# Bodenplatine.net
KiCad netlist of a schematic drawn in EAGLE
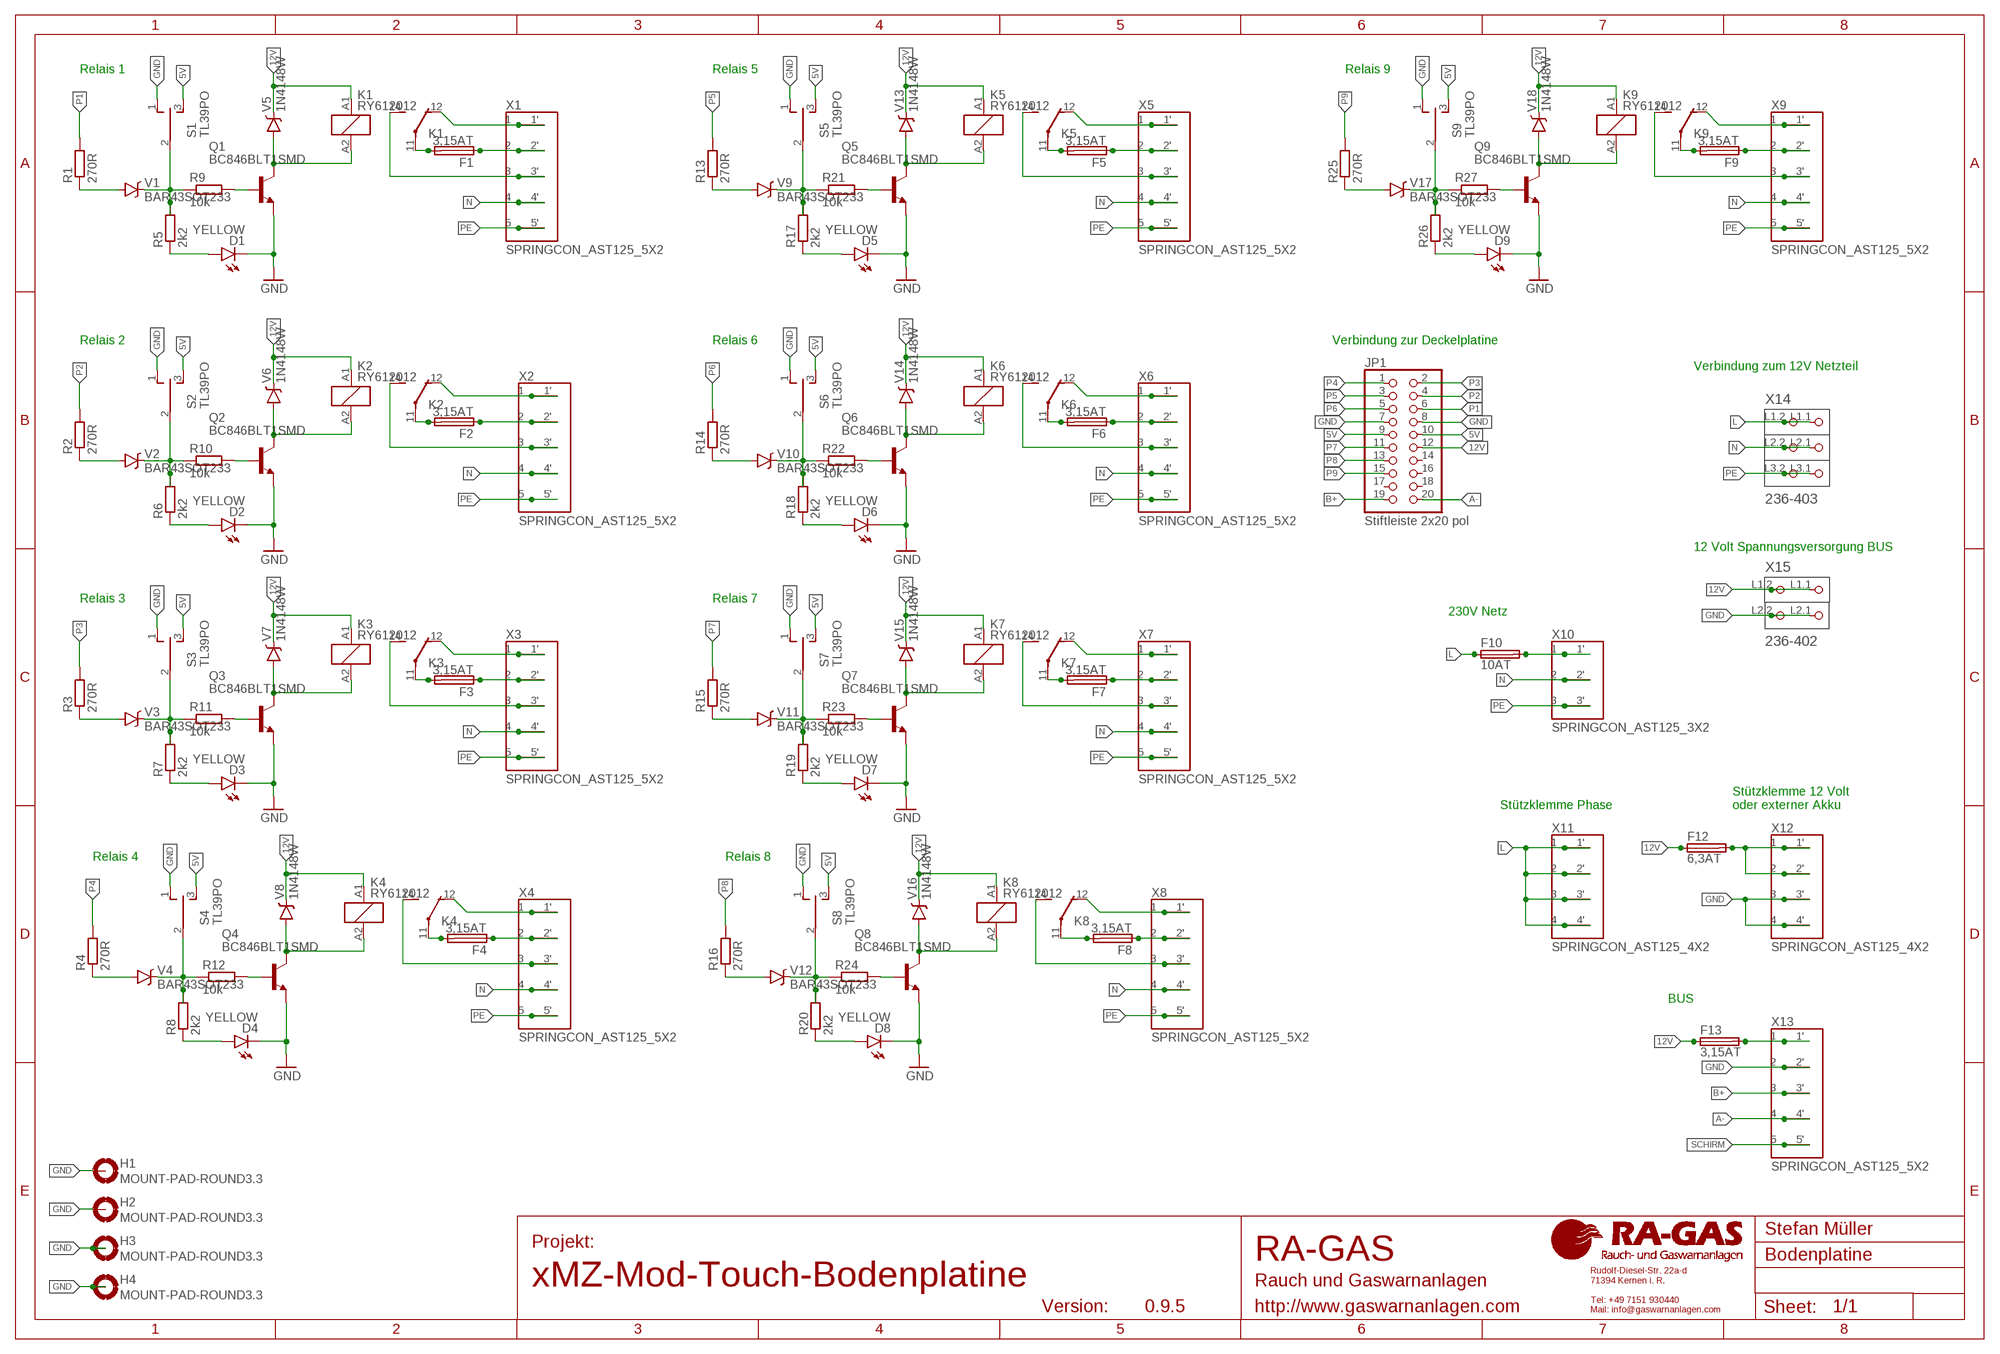
[diagram p0: schematic, sheet 1]

(export (version "E")
  (design (tool "Eeschema 10.0.6"))
  (components
    (comp (ref "D1")
      (value "YELLOW")
      (footprint "eagle-import:LED-1206")
      (fields (field (name "MF") "KINGBRIGHT") (field (name "MPN") "KP-3216SYC"))
      (libsource (lib "eagle-import") (part "LED-YELLOWLARGE"))
    )
    (comp (ref "D2")
      (value "YELLOW")
      (footprint "eagle-import:LED-1206")
      (fields (field (name "MF") "KINGBRIGHT") (field (name "MPN") "KP-3216SYC"))
      (libsource (lib "eagle-import") (part "LED-YELLOWLARGE"))
    )
    (comp (ref "D3")
      (value "YELLOW")
      (footprint "eagle-import:LED-1206")
      (fields (field (name "MF") "KINGBRIGHT") (field (name "MPN") "KP-3216SYC"))
      (libsource (lib "eagle-import") (part "LED-YELLOWLARGE"))
    )
    (comp (ref "D4")
      (value "YELLOW")
      (footprint "eagle-import:LED-1206")
      (fields (field (name "MF") "KINGBRIGHT") (field (name "MPN") "KP-3216SYC"))
      (libsource (lib "eagle-import") (part "LED-YELLOWLARGE"))
    )
    (comp (ref "D5")
      (value "YELLOW")
      (footprint "eagle-import:LED-1206")
      (fields (field (name "MF") "KINGBRIGHT") (field (name "MPN") "KP-3216SYC"))
      (libsource (lib "eagle-import") (part "LED-YELLOWLARGE"))
    )
    (comp (ref "D6")
      (value "YELLOW")
      (footprint "eagle-import:LED-1206")
      (fields (field (name "MF") "KINGBRIGHT") (field (name "MPN") "KP-3216SYC"))
      (libsource (lib "eagle-import") (part "LED-YELLOWLARGE"))
    )
    (comp (ref "D7")
      (value "YELLOW")
      (footprint "eagle-import:LED-1206")
      (fields (field (name "MF") "KINGBRIGHT") (field (name "MPN") "KP-3216SYC"))
      (libsource (lib "eagle-import") (part "LED-YELLOWLARGE"))
    )
    (comp (ref "D8")
      (value "YELLOW")
      (footprint "eagle-import:LED-1206")
      (fields (field (name "MF") "KINGBRIGHT") (field (name "MPN") "KP-3216SYC"))
      (libsource (lib "eagle-import") (part "LED-YELLOWLARGE"))
    )
    (comp (ref "D9")
      (value "YELLOW")
      (footprint "eagle-import:LED-1206")
      (fields (field (name "MF") "KINGBRIGHT") (field (name "MPN") "KP-3216SYC"))
      (libsource (lib "eagle-import") (part "LED-YELLOWLARGE"))
    )
    (comp (ref "F1")
      (value "3,15AT")
      (footprint "eagle-import:FPG4")
      (libsource (lib "eagle-import") (part "FPG4"))
    )
    (comp (ref "F2")
      (value "3,15AT")
      (footprint "eagle-import:FPG4")
      (libsource (lib "eagle-import") (part "FPG4"))
    )
    (comp (ref "F3")
      (value "3,15AT")
      (footprint "eagle-import:FPG4")
      (libsource (lib "eagle-import") (part "FPG4"))
    )
    (comp (ref "F4")
      (value "3,15AT")
      (footprint "eagle-import:FPG4")
      (libsource (lib "eagle-import") (part "FPG4"))
    )
    (comp (ref "F5")
      (value "3,15AT")
      (footprint "eagle-import:FPG4")
      (libsource (lib "eagle-import") (part "FPG4"))
    )
    (comp (ref "F6")
      (value "3,15AT")
      (footprint "eagle-import:FPG4")
      (libsource (lib "eagle-import") (part "FPG4"))
    )
    (comp (ref "F7")
      (value "3,15AT")
      (footprint "eagle-import:FPG4")
      (libsource (lib "eagle-import") (part "FPG4"))
    )
    (comp (ref "F8")
      (value "3,15AT")
      (footprint "eagle-import:FPG4")
      (libsource (lib "eagle-import") (part "FPG4"))
    )
    (comp (ref "F9")
      (value "3,15AT")
      (footprint "eagle-import:FPG4")
      (libsource (lib "eagle-import") (part "FPG4"))
    )
    (comp (ref "F10")
      (value "10AT")
      (footprint "eagle-import:FPG4")
      (libsource (lib "eagle-import") (part "FPG4"))
    )
    (comp (ref "F12")
      (value "6,3AT")
      (footprint "eagle-import:FPG4")
      (libsource (lib "eagle-import") (part "FPG4"))
    )
    (comp (ref "F13")
      (value "3,15AT")
      (footprint "eagle-import:FPG4")
      (libsource (lib "eagle-import") (part "FPG4"))
    )
    (comp (ref "H1")
      (value "MOUNT-PAD-ROUND3.3")
      (footprint "eagle-import:3,3-PAD")
      (libsource (lib "eagle-import") (part "MOUNT-PAD-ROUND3.3"))
    )
    (comp (ref "H2")
      (value "MOUNT-PAD-ROUND3.3")
      (footprint "eagle-import:3,3-PAD")
      (libsource (lib "eagle-import") (part "MOUNT-PAD-ROUND3.3"))
    )
    (comp (ref "H3")
      (value "MOUNT-PAD-ROUND3.3")
      (footprint "eagle-import:3,3-PAD")
      (libsource (lib "eagle-import") (part "MOUNT-PAD-ROUND3.3"))
    )
    (comp (ref "H4")
      (value "MOUNT-PAD-ROUND3.3")
      (footprint "eagle-import:3,3-PAD")
      (libsource (lib "eagle-import") (part "MOUNT-PAD-ROUND3.3"))
    )
    (comp (ref "JP1")
      (value "Stiftleiste 2x20 pol")
      (footprint "eagle-import:2X10")
      (fields (field (name "MF") "TE CONNECTIVITY / AMP") (field (name "MPN") "825440-5"))
      (libsource (lib "eagle-import") (part "PINHD-2X10"))
    )
    (comp (ref "K1")
      (value "RY612012")
      (footprint "eagle-import:RY-II")
      (fields
        (field (name "MF") "TYCO ELECTRONICS")
        (field (name "MF_1") "TE CONNECTIVITY / SCHRACK")
        (field (name "MPN") "V23061B1005A301")
        (field (name "OC_FARNELL") "1023958")
      )
      (libsource (lib "eagle-import") (part "RY?162012"))
    )
    (comp (ref "K2")
      (value "RY612012")
      (footprint "eagle-import:RY-II")
      (fields
        (field (name "MF") "TYCO ELECTRONICS")
        (field (name "MF_1") "TE CONNECTIVITY / SCHRACK")
        (field (name "MPN") "V23061B1005A301")
        (field (name "OC_FARNELL") "1023958")
      )
      (libsource (lib "eagle-import") (part "RY?162012"))
    )
    (comp (ref "K3")
      (value "RY612012")
      (footprint "eagle-import:RY-II")
      (fields
        (field (name "MF") "TYCO ELECTRONICS")
        (field (name "MF_1") "TE CONNECTIVITY / SCHRACK")
        (field (name "MPN") "V23061B1005A301")
        (field (name "OC_FARNELL") "1023958")
      )
      (libsource (lib "eagle-import") (part "RY?162012"))
    )
    (comp (ref "K4")
      (value "RY612012")
      (footprint "eagle-import:RY-II")
      (fields
        (field (name "MF") "TYCO ELECTRONICS")
        (field (name "MF_1") "TE CONNECTIVITY / SCHRACK")
        (field (name "MPN") "V23061B1005A301")
        (field (name "OC_FARNELL") "1023958")
      )
      (libsource (lib "eagle-import") (part "RY?162012"))
    )
    (comp (ref "K5")
      (value "RY612012")
      (footprint "eagle-import:RY-II")
      (fields
        (field (name "MF") "TYCO ELECTRONICS")
        (field (name "MF_1") "TE CONNECTIVITY / SCHRACK")
        (field (name "MPN") "V23061B1005A301")
        (field (name "OC_FARNELL") "1023958")
      )
      (libsource (lib "eagle-import") (part "RY?162012"))
    )
    (comp (ref "K6")
      (value "RY612012")
      (footprint "eagle-import:RY-II")
      (fields
        (field (name "MF") "TYCO ELECTRONICS")
        (field (name "MF_1") "TE CONNECTIVITY / SCHRACK")
        (field (name "MPN") "V23061B1005A301")
        (field (name "OC_FARNELL") "1023958")
      )
      (libsource (lib "eagle-import") (part "RY?162012"))
    )
    (comp (ref "K7")
      (value "RY612012")
      (footprint "eagle-import:RY-II")
      (fields
        (field (name "MF") "TYCO ELECTRONICS")
        (field (name "MF_1") "TE CONNECTIVITY / SCHRACK")
        (field (name "MPN") "V23061B1005A301")
        (field (name "OC_FARNELL") "1023958")
      )
      (libsource (lib "eagle-import") (part "RY?162012"))
    )
    (comp (ref "K8")
      (value "RY612012")
      (footprint "eagle-import:RY-II")
      (fields
        (field (name "MF") "TYCO ELECTRONICS")
        (field (name "MF_1") "TE CONNECTIVITY / SCHRACK")
        (field (name "MPN") "V23061B1005A301")
        (field (name "OC_FARNELL") "1023958")
      )
      (libsource (lib "eagle-import") (part "RY?162012"))
    )
    (comp (ref "K9")
      (value "RY612012")
      (footprint "eagle-import:RY-II")
      (fields
        (field (name "MF") "TYCO ELECTRONICS")
        (field (name "MF_1") "TE CONNECTIVITY / SCHRACK")
        (field (name "MPN") "V23061B1005A301")
        (field (name "OC_FARNELL") "1023958")
      )
      (libsource (lib "eagle-import") (part "RY?162012"))
    )
    (comp (ref "Q1")
      (value "BC846BLT1SMD")
      (footprint "eagle-import:SOT23")
      (fields (field (name "MF") "ON SEMICONDUCTOR") (field (name "MPN") "BC846BWT1G"))
      (libsource (lib "eagle-import") (part "BC846SMDBLT1"))
    )
    (comp (ref "Q2")
      (value "BC846BLT1SMD")
      (footprint "eagle-import:SOT23")
      (fields (field (name "MF") "ON SEMICONDUCTOR") (field (name "MPN") "BC846BWT1G"))
      (libsource (lib "eagle-import") (part "BC846SMDBLT1"))
    )
    (comp (ref "Q3")
      (value "BC846BLT1SMD")
      (footprint "eagle-import:SOT23")
      (fields (field (name "MF") "ON SEMICONDUCTOR") (field (name "MPN") "BC846BWT1G"))
      (libsource (lib "eagle-import") (part "BC846SMDBLT1"))
    )
    (comp (ref "Q4")
      (value "BC846BLT1SMD")
      (footprint "eagle-import:SOT23")
      (fields (field (name "MF") "ON SEMICONDUCTOR") (field (name "MPN") "BC846BWT1G"))
      (libsource (lib "eagle-import") (part "BC846SMDBLT1"))
    )
    (comp (ref "Q5")
      (value "BC846BLT1SMD")
      (footprint "eagle-import:SOT23")
      (fields (field (name "MF") "ON SEMICONDUCTOR") (field (name "MPN") "BC846BWT1G"))
      (libsource (lib "eagle-import") (part "BC846SMDBLT1"))
    )
    (comp (ref "Q6")
      (value "BC846BLT1SMD")
      (footprint "eagle-import:SOT23")
      (fields (field (name "MF") "ON SEMICONDUCTOR") (field (name "MPN") "BC846BWT1G"))
      (libsource (lib "eagle-import") (part "BC846SMDBLT1"))
    )
    (comp (ref "Q7")
      (value "BC846BLT1SMD")
      (footprint "eagle-import:SOT23")
      (fields (field (name "MF") "ON SEMICONDUCTOR") (field (name "MPN") "BC846BWT1G"))
      (libsource (lib "eagle-import") (part "BC846SMDBLT1"))
    )
    (comp (ref "Q8")
      (value "BC846BLT1SMD")
      (footprint "eagle-import:SOT23")
      (fields (field (name "MF") "ON SEMICONDUCTOR") (field (name "MPN") "BC846BWT1G"))
      (libsource (lib "eagle-import") (part "BC846SMDBLT1"))
    )
    (comp (ref "Q9")
      (value "BC846BLT1SMD")
      (footprint "eagle-import:SOT23")
      (fields (field (name "MF") "ON SEMICONDUCTOR") (field (name "MPN") "BC846BWT1G"))
      (libsource (lib "eagle-import") (part "BC846SMDBLT1"))
    )
    (comp (ref "R1")
      (value "270R")
      (footprint "eagle-import:M0805")
      (fields (field (name "MF") "MULTICOMP") (field (name "MPN") "MC01W08055270R"))
      (libsource (lib "eagle-import") (part "R-EU_M0805"))
    )
    (comp (ref "R2")
      (value "270R")
      (footprint "eagle-import:M0805")
      (fields (field (name "MF") "MULTICOMP") (field (name "MPN") "MC01W08055270R"))
      (libsource (lib "eagle-import") (part "R-EU_M0805"))
    )
    (comp (ref "R3")
      (value "270R")
      (footprint "eagle-import:M0805")
      (fields (field (name "MF") "MULTICOMP") (field (name "MPN") "MC01W08055270R"))
      (libsource (lib "eagle-import") (part "R-EU_M0805"))
    )
    (comp (ref "R4")
      (value "270R")
      (footprint "eagle-import:M0805")
      (fields (field (name "MF") "MULTICOMP") (field (name "MPN") "MC01W08055270R"))
      (libsource (lib "eagle-import") (part "R-EU_M0805"))
    )
    (comp (ref "R5")
      (value "2k2")
      (footprint "eagle-import:R0603")
      (fields (field (name "MF") "MULTICOMP") (field (name "MPN") "MC0063W060352K2"))
      (libsource (lib "eagle-import") (part "R-EU_R0603"))
    )
    (comp (ref "R6")
      (value "2k2")
      (footprint "eagle-import:R0603")
      (fields (field (name "MF") "MULTICOMP") (field (name "MPN") "MC0063W060352K2"))
      (libsource (lib "eagle-import") (part "R-EU_R0603"))
    )
    (comp (ref "R7")
      (value "2k2")
      (footprint "eagle-import:R0603")
      (fields (field (name "MF") "MULTICOMP") (field (name "MPN") "MC0063W060352K2"))
      (libsource (lib "eagle-import") (part "R-EU_R0603"))
    )
    (comp (ref "R8")
      (value "2k2")
      (footprint "eagle-import:R0603")
      (fields (field (name "MF") "MULTICOMP") (field (name "MPN") "MC0063W060352K2"))
      (libsource (lib "eagle-import") (part "R-EU_R0603"))
    )
    (comp (ref "R9")
      (value "10k")
      (footprint "eagle-import:R0603")
      (fields (field (name "MF") "TE CONNECTIVITY / NEOHM") (field (name "MPN") "CPF0603B10KE1"))
      (libsource (lib "eagle-import") (part "R-EU_R0603"))
    )
    (comp (ref "R10")
      (value "10k")
      (footprint "eagle-import:R0603")
      (fields (field (name "MF") "TE CONNECTIVITY / NEOHM") (field (name "MPN") "CPF0603B10KE1"))
      (libsource (lib "eagle-import") (part "R-EU_R0603"))
    )
    (comp (ref "R11")
      (value "10k")
      (footprint "eagle-import:R0603")
      (fields (field (name "MF") "TE CONNECTIVITY / NEOHM") (field (name "MPN") "CPF0603B10KE1"))
      (libsource (lib "eagle-import") (part "R-EU_R0603"))
    )
    (comp (ref "R12")
      (value "10k")
      (footprint "eagle-import:R0603")
      (fields (field (name "MF") "TE CONNECTIVITY / NEOHM") (field (name "MPN") "CPF0603B10KE1"))
      (libsource (lib "eagle-import") (part "R-EU_R0603"))
    )
    (comp (ref "R13")
      (value "270R")
      (footprint "eagle-import:M0805")
      (fields (field (name "MF") "MULTICOMP") (field (name "MPN") "MC01W08055270R"))
      (libsource (lib "eagle-import") (part "R-EU_M0805"))
    )
    (comp (ref "R14")
      (value "270R")
      (footprint "eagle-import:M0805")
      (fields (field (name "MF") "MULTICOMP") (field (name "MPN") "MC01W08055270R"))
      (libsource (lib "eagle-import") (part "R-EU_M0805"))
    )
    (comp (ref "R15")
      (value "270R")
      (footprint "eagle-import:M0805")
      (fields (field (name "MF") "MULTICOMP") (field (name "MPN") "MC01W08055270R"))
      (libsource (lib "eagle-import") (part "R-EU_M0805"))
    )
    (comp (ref "R16")
      (value "270R")
      (footprint "eagle-import:M0805")
      (fields (field (name "MF") "MULTICOMP") (field (name "MPN") "MC01W08055270R"))
      (libsource (lib "eagle-import") (part "R-EU_M0805"))
    )
    (comp (ref "R17")
      (value "2k2")
      (footprint "eagle-import:R0603")
      (fields (field (name "MF") "MULTICOMP") (field (name "MPN") "MC0063W060352K2"))
      (libsource (lib "eagle-import") (part "R-EU_R0603"))
    )
    (comp (ref "R18")
      (value "2k2")
      (footprint "eagle-import:R0603")
      (fields (field (name "MF") "MULTICOMP") (field (name "MPN") "MC0063W060352K2"))
      (libsource (lib "eagle-import") (part "R-EU_R0603"))
    )
    (comp (ref "R19")
      (value "2k2")
      (footprint "eagle-import:R0603")
      (fields (field (name "MF") "MULTICOMP") (field (name "MPN") "MC0063W060352K2"))
      (libsource (lib "eagle-import") (part "R-EU_R0603"))
    )
    (comp (ref "R20")
      (value "2k2")
      (footprint "eagle-import:R0603")
      (fields (field (name "MF") "MULTICOMP") (field (name "MPN") "MC0063W060352K2"))
      (libsource (lib "eagle-import") (part "R-EU_R0603"))
    )
    (comp (ref "R21")
      (value "10k")
      (footprint "eagle-import:R0603")
      (fields (field (name "MF") "TE CONNECTIVITY / NEOHM") (field (name "MPN") "CPF0603B10KE1"))
      (libsource (lib "eagle-import") (part "R-EU_R0603"))
    )
    (comp (ref "R22")
      (value "10k")
      (footprint "eagle-import:R0603")
      (fields (field (name "MF") "TE CONNECTIVITY / NEOHM") (field (name "MPN") "CPF0603B10KE1"))
      (libsource (lib "eagle-import") (part "R-EU_R0603"))
    )
    (comp (ref "R23")
      (value "10k")
      (footprint "eagle-import:R0603")
      (fields (field (name "MF") "TE CONNECTIVITY / NEOHM") (field (name "MPN") "CPF0603B10KE1"))
      (libsource (lib "eagle-import") (part "R-EU_R0603"))
    )
    (comp (ref "R24")
      (value "10k")
      (footprint "eagle-import:R0603")
      (fields (field (name "MF") "TE CONNECTIVITY / NEOHM") (field (name "MPN") "CPF0603B10KE1"))
      (libsource (lib "eagle-import") (part "R-EU_R0603"))
    )
    (comp (ref "R25")
      (value "270R")
      (footprint "eagle-import:M0805")
      (fields (field (name "MF") "MULTICOMP") (field (name "MPN") "MC01W08055270R"))
      (libsource (lib "eagle-import") (part "R-EU_M0805"))
    )
    (comp (ref "R26")
      (value "2k2")
      (footprint "eagle-import:R0603")
      (fields (field (name "MF") "MULTICOMP") (field (name "MPN") "MC0063W060352K2"))
      (libsource (lib "eagle-import") (part "R-EU_R0603"))
    )
    (comp (ref "R27")
      (value "10k")
      (footprint "eagle-import:R0603")
      (fields (field (name "MF") "TE CONNECTIVITY / NEOHM") (field (name "MPN") "CPF0603B10KE1"))
      (libsource (lib "eagle-import") (part "R-EU_R0603"))
    )
    (comp (ref "S1")
      (value "TL39PO")
      (footprint "eagle-import:TL3XPO")
      (fields (field (name "MF") "TE CONNECTIVITY / ALCOSWITCH") (field (name "MPN") "A103SYCQ04"))
      (libsource (lib "eagle-import") (part "TL39PO"))
    )
    (comp (ref "S2")
      (value "TL39PO")
      (footprint "eagle-import:TL3XPO")
      (fields (field (name "MF") "TE CONNECTIVITY / ALCOSWITCH") (field (name "MPN") "A103SYCQ04"))
      (libsource (lib "eagle-import") (part "TL39PO"))
    )
    (comp (ref "S3")
      (value "TL39PO")
      (footprint "eagle-import:TL3XPO")
      (fields (field (name "MF") "TE CONNECTIVITY / ALCOSWITCH") (field (name "MPN") "A103SYCQ04"))
      (libsource (lib "eagle-import") (part "TL39PO"))
    )
    (comp (ref "S4")
      (value "TL39PO")
      (footprint "eagle-import:TL3XPO")
      (fields (field (name "MF") "TE CONNECTIVITY / ALCOSWITCH") (field (name "MPN") "A103SYCQ04"))
      (libsource (lib "eagle-import") (part "TL39PO"))
    )
    (comp (ref "S5")
      (value "TL39PO")
      (footprint "eagle-import:TL3XPO")
      (fields (field (name "MF") "TE CONNECTIVITY / ALCOSWITCH") (field (name "MPN") "A103SYCQ04"))
      (libsource (lib "eagle-import") (part "TL39PO"))
    )
    (comp (ref "S6")
      (value "TL39PO")
      (footprint "eagle-import:TL3XPO")
      (fields (field (name "MF") "TE CONNECTIVITY / ALCOSWITCH") (field (name "MPN") "A103SYCQ04"))
      (libsource (lib "eagle-import") (part "TL39PO"))
    )
    (comp (ref "S7")
      (value "TL39PO")
      (footprint "eagle-import:TL3XPO")
      (fields (field (name "MF") "TE CONNECTIVITY / ALCOSWITCH") (field (name "MPN") "A103SYCQ04"))
      (libsource (lib "eagle-import") (part "TL39PO"))
    )
    (comp (ref "S8")
      (value "TL39PO")
      (footprint "eagle-import:TL3XPO")
      (fields (field (name "MF") "TE CONNECTIVITY / ALCOSWITCH") (field (name "MPN") "A103SYCQ04"))
      (libsource (lib "eagle-import") (part "TL39PO"))
    )
    (comp (ref "S9")
      (value "TL39PO")
      (footprint "eagle-import:TL3XPO")
      (fields (field (name "MF") "TE CONNECTIVITY / ALCOSWITCH") (field (name "MPN") "A103SYCQ04"))
      (libsource (lib "eagle-import") (part "TL39PO"))
    )
    (comp (ref "V1")
      (value "BAR43SOT233")
      (footprint "eagle-import:SOT23")
      (fields (field (name "MF") "FAIRCHILD SEMICONDUCTOR") (field (name "MPN") "BAR43"))
      (libsource (lib "eagle-import") (part "BAR43SOT233"))
    )
    (comp (ref "V2")
      (value "BAR43SOT233")
      (footprint "eagle-import:SOT23")
      (fields (field (name "MF") "FAIRCHILD SEMICONDUCTOR") (field (name "MPN") "BAR43"))
      (libsource (lib "eagle-import") (part "BAR43SOT233"))
    )
    (comp (ref "V3")
      (value "BAR43SOT233")
      (footprint "eagle-import:SOT23")
      (fields (field (name "MF") "FAIRCHILD SEMICONDUCTOR") (field (name "MPN") "BAR43"))
      (libsource (lib "eagle-import") (part "BAR43SOT233"))
    )
    (comp (ref "V4")
      (value "BAR43SOT233")
      (footprint "eagle-import:SOT23")
      (fields (field (name "MF") "FAIRCHILD SEMICONDUCTOR") (field (name "MPN") "BAR43"))
      (libsource (lib "eagle-import") (part "BAR43SOT233"))
    )
    (comp (ref "V5")
      (value "1N4148W")
      (footprint "eagle-import:MINIMELF")
      (fields (field (name "MF") "VISHAY") (field (name "MPN") "LL4148-GS08"))
      (libsource (lib "eagle-import") (part "LL4148"))
    )
    (comp (ref "V6")
      (value "1N4148W")
      (footprint "eagle-import:MINIMELF")
      (fields (field (name "MF") "VISHAY") (field (name "MPN") "LL4148-GS08"))
      (libsource (lib "eagle-import") (part "LL4148"))
    )
    (comp (ref "V7")
      (value "1N4148W")
      (footprint "eagle-import:MINIMELF")
      (fields (field (name "MF") "VISHAY") (field (name "MPN") "LL4148-GS08"))
      (libsource (lib "eagle-import") (part "LL4148"))
    )
    (comp (ref "V8")
      (value "1N4148W")
      (footprint "eagle-import:MINIMELF")
      (fields (field (name "MF") "VISHAY") (field (name "MPN") "LL4148-GS08"))
      (libsource (lib "eagle-import") (part "LL4148"))
    )
    (comp (ref "V9")
      (value "BAR43SOT233")
      (footprint "eagle-import:SOT23")
      (fields (field (name "MF") "FAIRCHILD SEMICONDUCTOR") (field (name "MPN") "BAR43"))
      (libsource (lib "eagle-import") (part "BAR43SOT233"))
    )
    (comp (ref "V10")
      (value "BAR43SOT233")
      (footprint "eagle-import:SOT23")
      (fields (field (name "MF") "FAIRCHILD SEMICONDUCTOR") (field (name "MPN") "BAR43"))
      (libsource (lib "eagle-import") (part "BAR43SOT233"))
    )
    (comp (ref "V11")
      (value "BAR43SOT233")
      (footprint "eagle-import:SOT23")
      (fields (field (name "MF") "FAIRCHILD SEMICONDUCTOR") (field (name "MPN") "BAR43"))
      (libsource (lib "eagle-import") (part "BAR43SOT233"))
    )
    (comp (ref "V12")
      (value "BAR43SOT233")
      (footprint "eagle-import:SOT23")
      (fields (field (name "MF") "FAIRCHILD SEMICONDUCTOR") (field (name "MPN") "BAR43"))
      (libsource (lib "eagle-import") (part "BAR43SOT233"))
    )
    (comp (ref "V13")
      (value "1N4148W")
      (footprint "eagle-import:MINIMELF")
      (fields (field (name "MF") "VISHAY") (field (name "MPN") "LL4148-GS08"))
      (libsource (lib "eagle-import") (part "LL4148"))
    )
    (comp (ref "V14")
      (value "1N4148W")
      (footprint "eagle-import:MINIMELF")
      (fields (field (name "MF") "VISHAY") (field (name "MPN") "LL4148-GS08"))
      (libsource (lib "eagle-import") (part "LL4148"))
    )
    (comp (ref "V15")
      (value "1N4148W")
      (footprint "eagle-import:MINIMELF")
      (fields (field (name "MF") "VISHAY") (field (name "MPN") "LL4148-GS08"))
      (libsource (lib "eagle-import") (part "LL4148"))
    )
    (comp (ref "V16")
      (value "1N4148W")
      (footprint "eagle-import:MINIMELF")
      (fields (field (name "MF") "VISHAY") (field (name "MPN") "LL4148-GS08"))
      (libsource (lib "eagle-import") (part "LL4148"))
    )
    (comp (ref "V17")
      (value "BAR43SOT233")
      (footprint "eagle-import:SOT23")
      (fields (field (name "MF") "FAIRCHILD SEMICONDUCTOR") (field (name "MPN") "BAR43"))
      (libsource (lib "eagle-import") (part "BAR43SOT233"))
    )
    (comp (ref "V18")
      (value "1N4148W")
      (footprint "eagle-import:MINIMELF")
      (fields (field (name "MF") "VISHAY") (field (name "MPN") "LL4148-GS08"))
      (libsource (lib "eagle-import") (part "LL4148"))
    )
    (comp (ref "X1")
      (value "SPRINGCON_AST125_5X2")
      (footprint "eagle-import:SPRINGCON_AST125_5X2")
      (libsource (lib "eagle-import") (part "SPRINGCON_AST125_5X2"))
    )
    (comp (ref "X2")
      (value "SPRINGCON_AST125_5X2")
      (footprint "eagle-import:SPRINGCON_AST125_5X2")
      (libsource (lib "eagle-import") (part "SPRINGCON_AST125_5X2"))
    )
    (comp (ref "X3")
      (value "SPRINGCON_AST125_5X2")
      (footprint "eagle-import:SPRINGCON_AST125_5X2")
      (libsource (lib "eagle-import") (part "SPRINGCON_AST125_5X2"))
    )
    (comp (ref "X4")
      (value "SPRINGCON_AST125_5X2")
      (footprint "eagle-import:SPRINGCON_AST125_5X2")
      (libsource (lib "eagle-import") (part "SPRINGCON_AST125_5X2"))
    )
    (comp (ref "X5")
      (value "SPRINGCON_AST125_5X2")
      (footprint "eagle-import:SPRINGCON_AST125_5X2")
      (libsource (lib "eagle-import") (part "SPRINGCON_AST125_5X2"))
    )
    (comp (ref "X6")
      (value "SPRINGCON_AST125_5X2")
      (footprint "eagle-import:SPRINGCON_AST125_5X2")
      (libsource (lib "eagle-import") (part "SPRINGCON_AST125_5X2"))
    )
    (comp (ref "X7")
      (value "SPRINGCON_AST125_5X2")
      (footprint "eagle-import:SPRINGCON_AST125_5X2")
      (libsource (lib "eagle-import") (part "SPRINGCON_AST125_5X2"))
    )
    (comp (ref "X8")
      (value "SPRINGCON_AST125_5X2")
      (footprint "eagle-import:SPRINGCON_AST125_5X2")
      (libsource (lib "eagle-import") (part "SPRINGCON_AST125_5X2"))
    )
    (comp (ref "X9")
      (value "SPRINGCON_AST125_5X2")
      (footprint "eagle-import:SPRINGCON_AST125_5X2")
      (libsource (lib "eagle-import") (part "SPRINGCON_AST125_5X2"))
    )
    (comp (ref "X10")
      (value "SPRINGCON_AST125_3X2")
      (footprint "eagle-import:SPRINGCON_AST125_3X2")
      (libsource (lib "eagle-import") (part "SPRINGCON_AST125_3X2"))
    )
    (comp (ref "X11")
      (value "SPRINGCON_AST125_4X2")
      (footprint "eagle-import:SPRINGCON_AST125_4X2")
      (libsource (lib "eagle-import") (part "SPRINGCON_AST125_4X2"))
    )
    (comp (ref "X12")
      (value "SPRINGCON_AST125_4X2")
      (footprint "eagle-import:SPRINGCON_AST125_4X2")
      (libsource (lib "eagle-import") (part "SPRINGCON_AST125_4X2"))
    )
    (comp (ref "X13")
      (value "SPRINGCON_AST125_5X2")
      (footprint "eagle-import:SPRINGCON_AST125_5X2")
      (libsource (lib "eagle-import") (part "SPRINGCON_AST125_5X2"))
    )
    (comp (ref "X14")
      (value "236-403")
      (footprint "eagle-import:P-236-403")
      (fields (field (name "MF") "WAGO"))
      (libsource (lib "eagle-import") (part "236-403"))
    )
    (comp (ref "X15")
      (value "236-402")
      (footprint "eagle-import:P-236-402")
      (fields (field (name "MF") "WAGO"))
      (libsource (lib "eagle-import") (part "236-402"))
    )
  )
  (nets
    (net (code "1") (name "5V") (class "Default")
      (node (ref "JP1") (pin "10") (pinfunction "10_10") (pintype "passive"))
      (node (ref "JP1") (pin "9") (pinfunction "9_9") (pintype "passive"))
      (node (ref "S1") (pin "3") (pinfunction "S_3") (pintype "passive"))
      (node (ref "S2") (pin "3") (pinfunction "S_3") (pintype "passive"))
      (node (ref "S3") (pin "3") (pinfunction "S_3") (pintype "passive"))
      (node (ref "S4") (pin "3") (pinfunction "S_3") (pintype "passive"))
      (node (ref "S5") (pin "3") (pinfunction "S_3") (pintype "passive"))
      (node (ref "S6") (pin "3") (pinfunction "S_3") (pintype "passive"))
      (node (ref "S7") (pin "3") (pinfunction "S_3") (pintype "passive"))
      (node (ref "S8") (pin "3") (pinfunction "S_3") (pintype "passive"))
      (node (ref "S9") (pin "3") (pinfunction "S_3") (pintype "passive"))
    )
    (net (code "2") (name "12V") (class "Default")
      (node (ref "F12") (pin "1") (pinfunction "1_1") (pintype "passive"))
      (node (ref "F12") (pin "1'") (pinfunction "1_1'") (pintype "passive"))
      (node (ref "F13") (pin "1") (pinfunction "1_1") (pintype "passive"))
      (node (ref "F13") (pin "1'") (pinfunction "1_1'") (pintype "passive"))
      (node (ref "JP1") (pin "12") (pinfunction "12_12") (pintype "passive"))
      (node (ref "K1") (pin "A1") (pinfunction "1_A1") (pintype "passive"))
      (node (ref "K2") (pin "A1") (pinfunction "1_A1") (pintype "passive"))
      (node (ref "K3") (pin "A1") (pinfunction "1_A1") (pintype "passive"))
      (node (ref "K4") (pin "A1") (pinfunction "1_A1") (pintype "passive"))
      (node (ref "K5") (pin "A1") (pinfunction "1_A1") (pintype "passive"))
      (node (ref "K6") (pin "A1") (pinfunction "1_A1") (pintype "passive"))
      (node (ref "K7") (pin "A1") (pinfunction "1_A1") (pintype "passive"))
      (node (ref "K8") (pin "A1") (pinfunction "1_A1") (pintype "passive"))
      (node (ref "K9") (pin "A1") (pinfunction "1_A1") (pintype "passive"))
      (node (ref "V13") (pin "C") (pinfunction "C_C") (pintype "passive"))
      (node (ref "V14") (pin "C") (pinfunction "C_C") (pintype "passive"))
      (node (ref "V15") (pin "C") (pinfunction "C_C") (pintype "passive"))
      (node (ref "V16") (pin "C") (pinfunction "C_C") (pintype "passive"))
      (node (ref "V18") (pin "C") (pinfunction "C_C") (pintype "passive"))
      (node (ref "V5") (pin "C") (pinfunction "C_C") (pintype "passive"))
      (node (ref "V6") (pin "C") (pinfunction "C_C") (pintype "passive"))
      (node (ref "V7") (pin "C") (pinfunction "C_C") (pintype "passive"))
      (node (ref "V8") (pin "C") (pinfunction "C_C") (pintype "passive"))
      (node (ref "X15") (pin "L1.1") (pinfunction "P1.1_L1.1") (pintype "bidirectional"))
      (node (ref "X15") (pin "L1.2") (pinfunction "P1.2_L1.2") (pintype "bidirectional"))
    )
    (net (code "3") (name "A-") (class "Default")
      (node (ref "JP1") (pin "20") (pinfunction "20_20") (pintype "passive"))
      (node (ref "X13") (pin "4") (pinfunction "4_4") (pintype "passive"))
      (node (ref "X13") (pin "4'") (pinfunction "4_4'") (pintype "passive"))
    )
    (net (code "4") (name "B+") (class "Default")
      (node (ref "JP1") (pin "19") (pinfunction "19_19") (pintype "passive"))
      (node (ref "X13") (pin "3") (pinfunction "3_3") (pintype "passive"))
      (node (ref "X13") (pin "3'") (pinfunction "3_3'") (pintype "passive"))
    )
    (net (code "5") (name "GND") (class "Default")
      (node (ref "D1") (pin "C") (pinfunction "C_C") (pintype "passive"))
      (node (ref "D2") (pin "C") (pinfunction "C_C") (pintype "passive"))
      (node (ref "D3") (pin "C") (pinfunction "C_C") (pintype "passive"))
      (node (ref "D4") (pin "C") (pinfunction "C_C") (pintype "passive"))
      (node (ref "D5") (pin "C") (pinfunction "C_C") (pintype "passive"))
      (node (ref "D6") (pin "C") (pinfunction "C_C") (pintype "passive"))
      (node (ref "D7") (pin "C") (pinfunction "C_C") (pintype "passive"))
      (node (ref "D8") (pin "C") (pinfunction "C_C") (pintype "passive"))
      (node (ref "D9") (pin "C") (pinfunction "C_C") (pintype "passive"))
      (node (ref "H1") (pin "B3,3") (pinfunction "MOUNT_B3,3") (pintype "passive"))
      (node (ref "H2") (pin "B3,3") (pinfunction "MOUNT_B3,3") (pintype "passive"))
      (node (ref "H3") (pin "B3,3") (pinfunction "MOUNT_B3,3") (pintype "passive"))
      (node (ref "H4") (pin "B3,3") (pinfunction "MOUNT_B3,3") (pintype "passive"))
      (node (ref "JP1") (pin "7") (pinfunction "7_7") (pintype "passive"))
      (node (ref "JP1") (pin "8") (pinfunction "8_8") (pintype "passive"))
      (node (ref "Q1") (pin "2") (pinfunction "E_2") (pintype "passive"))
      (node (ref "Q2") (pin "2") (pinfunction "E_2") (pintype "passive"))
      (node (ref "Q3") (pin "2") (pinfunction "E_2") (pintype "passive"))
      (node (ref "Q4") (pin "2") (pinfunction "E_2") (pintype "passive"))
      (node (ref "Q5") (pin "2") (pinfunction "E_2") (pintype "passive"))
      (node (ref "Q6") (pin "2") (pinfunction "E_2") (pintype "passive"))
      (node (ref "Q7") (pin "2") (pinfunction "E_2") (pintype "passive"))
      (node (ref "Q8") (pin "2") (pinfunction "E_2") (pintype "passive"))
      (node (ref "Q9") (pin "2") (pinfunction "E_2") (pintype "passive"))
      (node (ref "S1") (pin "1") (pinfunction "O_1") (pintype "passive"))
      (node (ref "S2") (pin "1") (pinfunction "O_1") (pintype "passive"))
      (node (ref "S3") (pin "1") (pinfunction "O_1") (pintype "passive"))
      (node (ref "S4") (pin "1") (pinfunction "O_1") (pintype "passive"))
      (node (ref "S5") (pin "1") (pinfunction "O_1") (pintype "passive"))
      (node (ref "S6") (pin "1") (pinfunction "O_1") (pintype "passive"))
      (node (ref "S7") (pin "1") (pinfunction "O_1") (pintype "passive"))
      (node (ref "S8") (pin "1") (pinfunction "O_1") (pintype "passive"))
      (node (ref "S9") (pin "1") (pinfunction "O_1") (pintype "passive"))
      (node (ref "X12") (pin "3") (pinfunction "3_3") (pintype "passive"))
      (node (ref "X12") (pin "3'") (pinfunction "3_3'") (pintype "passive"))
      (node (ref "X12") (pin "4") (pinfunction "4_4") (pintype "passive"))
      (node (ref "X12") (pin "4'") (pinfunction "4_4'") (pintype "passive"))
      (node (ref "X13") (pin "2") (pinfunction "2_2") (pintype "passive"))
      (node (ref "X13") (pin "2'") (pinfunction "2_2'") (pintype "passive"))
      (node (ref "X15") (pin "L2.1") (pinfunction "P2.1_L2.1") (pintype "bidirectional"))
      (node (ref "X15") (pin "L2.2") (pinfunction "P2.2_L2.2") (pintype "bidirectional"))
    )
    (net (code "6") (name "L") (class "Default")
      (node (ref "F10") (pin "1") (pinfunction "1_1") (pintype "passive"))
      (node (ref "F10") (pin "1'") (pinfunction "1_1'") (pintype "passive"))
      (node (ref "X11") (pin "1") (pinfunction "1_1") (pintype "passive"))
      (node (ref "X11") (pin "1'") (pinfunction "1_1'") (pintype "passive"))
      (node (ref "X11") (pin "2") (pinfunction "2_2") (pintype "passive"))
      (node (ref "X11") (pin "2'") (pinfunction "2_2'") (pintype "passive"))
      (node (ref "X11") (pin "3") (pinfunction "3_3") (pintype "passive"))
      (node (ref "X11") (pin "3'") (pinfunction "3_3'") (pintype "passive"))
      (node (ref "X11") (pin "4") (pinfunction "4_4") (pintype "passive"))
      (node (ref "X11") (pin "4'") (pinfunction "4_4'") (pintype "passive"))
      (node (ref "X14") (pin "L1.1") (pinfunction "P1.1_L1.1") (pintype "bidirectional"))
      (node (ref "X14") (pin "L1.2") (pinfunction "P1.2_L1.2") (pintype "bidirectional"))
    )
    (net (code "7") (name "N") (class "Default")
      (node (ref "X1") (pin "4") (pinfunction "4_4") (pintype "passive"))
      (node (ref "X1") (pin "4'") (pinfunction "4_4'") (pintype "passive"))
      (node (ref "X10") (pin "2") (pinfunction "2_2") (pintype "passive"))
      (node (ref "X10") (pin "2'") (pinfunction "2_2'") (pintype "passive"))
      (node (ref "X14") (pin "L2.1") (pinfunction "P2.1_L2.1") (pintype "bidirectional"))
      (node (ref "X14") (pin "L2.2") (pinfunction "P2.2_L2.2") (pintype "bidirectional"))
      (node (ref "X2") (pin "4") (pinfunction "4_4") (pintype "passive"))
      (node (ref "X2") (pin "4'") (pinfunction "4_4'") (pintype "passive"))
      (node (ref "X3") (pin "4") (pinfunction "4_4") (pintype "passive"))
      (node (ref "X3") (pin "4'") (pinfunction "4_4'") (pintype "passive"))
      (node (ref "X4") (pin "4") (pinfunction "4_4") (pintype "passive"))
      (node (ref "X4") (pin "4'") (pinfunction "4_4'") (pintype "passive"))
      (node (ref "X5") (pin "4") (pinfunction "4_4") (pintype "passive"))
      (node (ref "X5") (pin "4'") (pinfunction "4_4'") (pintype "passive"))
      (node (ref "X6") (pin "4") (pinfunction "4_4") (pintype "passive"))
      (node (ref "X6") (pin "4'") (pinfunction "4_4'") (pintype "passive"))
      (node (ref "X7") (pin "4") (pinfunction "4_4") (pintype "passive"))
      (node (ref "X7") (pin "4'") (pinfunction "4_4'") (pintype "passive"))
      (node (ref "X8") (pin "4") (pinfunction "4_4") (pintype "passive"))
      (node (ref "X8") (pin "4'") (pinfunction "4_4'") (pintype "passive"))
      (node (ref "X9") (pin "4") (pinfunction "4_4") (pintype "passive"))
      (node (ref "X9") (pin "4'") (pinfunction "4_4'") (pintype "passive"))
    )
    (net (code "8") (name "Net-(D1-PadA)") (class "Default")
      (node (ref "D1") (pin "A") (pinfunction "A_A") (pintype "passive"))
      (node (ref "R5") (pin "1") (pinfunction "1_1") (pintype "passive"))
    )
    (net (code "9") (name "Net-(D2-PadA)") (class "Default")
      (node (ref "D2") (pin "A") (pinfunction "A_A") (pintype "passive"))
      (node (ref "R6") (pin "1") (pinfunction "1_1") (pintype "passive"))
    )
    (net (code "10") (name "Net-(D3-PadA)") (class "Default")
      (node (ref "D3") (pin "A") (pinfunction "A_A") (pintype "passive"))
      (node (ref "R7") (pin "1") (pinfunction "1_1") (pintype "passive"))
    )
    (net (code "11") (name "Net-(D4-PadA)") (class "Default")
      (node (ref "D4") (pin "A") (pinfunction "A_A") (pintype "passive"))
      (node (ref "R8") (pin "1") (pinfunction "1_1") (pintype "passive"))
    )
    (net (code "12") (name "Net-(D5-PadA)") (class "Default")
      (node (ref "D5") (pin "A") (pinfunction "A_A") (pintype "passive"))
      (node (ref "R17") (pin "1") (pinfunction "1_1") (pintype "passive"))
    )
    (net (code "13") (name "Net-(D6-PadA)") (class "Default")
      (node (ref "D6") (pin "A") (pinfunction "A_A") (pintype "passive"))
      (node (ref "R18") (pin "1") (pinfunction "1_1") (pintype "passive"))
    )
    (net (code "14") (name "Net-(D7-PadA)") (class "Default")
      (node (ref "D7") (pin "A") (pinfunction "A_A") (pintype "passive"))
      (node (ref "R19") (pin "1") (pinfunction "1_1") (pintype "passive"))
    )
    (net (code "15") (name "Net-(D8-PadA)") (class "Default")
      (node (ref "D8") (pin "A") (pinfunction "A_A") (pintype "passive"))
      (node (ref "R20") (pin "1") (pinfunction "1_1") (pintype "passive"))
    )
    (net (code "16") (name "Net-(D9-PadA)") (class "Default")
      (node (ref "D9") (pin "A") (pinfunction "A_A") (pintype "passive"))
      (node (ref "R26") (pin "1") (pinfunction "1_1") (pintype "passive"))
    )
    (net (code "17") (name "Net-(F1-1-Pad1')") (class "Default")
      (node (ref "F1") (pin "1") (pinfunction "1_1") (pintype "passive"))
      (node (ref "F1") (pin "1'") (pinfunction "1_1'") (pintype "passive"))
      (node (ref "X1") (pin "2") (pinfunction "2_2") (pintype "passive"))
      (node (ref "X1") (pin "2'") (pinfunction "2_2'") (pintype "passive"))
    )
    (net (code "18") (name "Net-(F2-1-Pad1')") (class "Default")
      (node (ref "F2") (pin "1") (pinfunction "1_1") (pintype "passive"))
      (node (ref "F2") (pin "1'") (pinfunction "1_1'") (pintype "passive"))
      (node (ref "X2") (pin "2") (pinfunction "2_2") (pintype "passive"))
      (node (ref "X2") (pin "2'") (pinfunction "2_2'") (pintype "passive"))
    )
    (net (code "19") (name "Net-(F3-1-Pad1')") (class "Default")
      (node (ref "F3") (pin "1") (pinfunction "1_1") (pintype "passive"))
      (node (ref "F3") (pin "1'") (pinfunction "1_1'") (pintype "passive"))
      (node (ref "X3") (pin "2") (pinfunction "2_2") (pintype "passive"))
      (node (ref "X3") (pin "2'") (pinfunction "2_2'") (pintype "passive"))
    )
    (net (code "20") (name "Net-(F4-1-Pad1')") (class "Default")
      (node (ref "F4") (pin "1") (pinfunction "1_1") (pintype "passive"))
      (node (ref "F4") (pin "1'") (pinfunction "1_1'") (pintype "passive"))
      (node (ref "X4") (pin "2") (pinfunction "2_2") (pintype "passive"))
      (node (ref "X4") (pin "2'") (pinfunction "2_2'") (pintype "passive"))
    )
    (net (code "21") (name "Net-(F5-1-Pad1')") (class "Default")
      (node (ref "F5") (pin "1") (pinfunction "1_1") (pintype "passive"))
      (node (ref "F5") (pin "1'") (pinfunction "1_1'") (pintype "passive"))
      (node (ref "X5") (pin "2") (pinfunction "2_2") (pintype "passive"))
      (node (ref "X5") (pin "2'") (pinfunction "2_2'") (pintype "passive"))
    )
    (net (code "22") (name "Net-(F6-1-Pad1')") (class "Default")
      (node (ref "F6") (pin "1") (pinfunction "1_1") (pintype "passive"))
      (node (ref "F6") (pin "1'") (pinfunction "1_1'") (pintype "passive"))
      (node (ref "X6") (pin "2") (pinfunction "2_2") (pintype "passive"))
      (node (ref "X6") (pin "2'") (pinfunction "2_2'") (pintype "passive"))
    )
    (net (code "23") (name "Net-(F7-1-Pad1')") (class "Default")
      (node (ref "F7") (pin "1") (pinfunction "1_1") (pintype "passive"))
      (node (ref "F7") (pin "1'") (pinfunction "1_1'") (pintype "passive"))
      (node (ref "X7") (pin "2") (pinfunction "2_2") (pintype "passive"))
      (node (ref "X7") (pin "2'") (pinfunction "2_2'") (pintype "passive"))
    )
    (net (code "24") (name "Net-(F8-1-Pad1')") (class "Default")
      (node (ref "F8") (pin "1") (pinfunction "1_1") (pintype "passive"))
      (node (ref "F8") (pin "1'") (pinfunction "1_1'") (pintype "passive"))
      (node (ref "X8") (pin "2") (pinfunction "2_2") (pintype "passive"))
      (node (ref "X8") (pin "2'") (pinfunction "2_2'") (pintype "passive"))
    )
    (net (code "25") (name "Net-(F9-1-Pad1')") (class "Default")
      (node (ref "F9") (pin "1") (pinfunction "1_1") (pintype "passive"))
      (node (ref "F9") (pin "1'") (pinfunction "1_1'") (pintype "passive"))
      (node (ref "X9") (pin "2") (pinfunction "2_2") (pintype "passive"))
      (node (ref "X9") (pin "2'") (pinfunction "2_2'") (pintype "passive"))
    )
    (net (code "26") (name "Net-(F10-2-Pad2')") (class "Default")
      (node (ref "F10") (pin "2") (pinfunction "2_2") (pintype "passive"))
      (node (ref "F10") (pin "2'") (pinfunction "2_2'") (pintype "passive"))
      (node (ref "X10") (pin "1") (pinfunction "1_1") (pintype "passive"))
      (node (ref "X10") (pin "1'") (pinfunction "1_1'") (pintype "passive"))
    )
    (net (code "27") (name "Net-(F12-2-Pad2')") (class "Default")
      (node (ref "F12") (pin "2") (pinfunction "2_2") (pintype "passive"))
      (node (ref "F12") (pin "2'") (pinfunction "2_2'") (pintype "passive"))
      (node (ref "X12") (pin "1") (pinfunction "1_1") (pintype "passive"))
      (node (ref "X12") (pin "1'") (pinfunction "1_1'") (pintype "passive"))
      (node (ref "X12") (pin "2") (pinfunction "2_2") (pintype "passive"))
      (node (ref "X12") (pin "2'") (pinfunction "2_2'") (pintype "passive"))
    )
    (net (code "28") (name "Net-(F13-2-Pad2')") (class "Default")
      (node (ref "F13") (pin "2") (pinfunction "2_2") (pintype "passive"))
      (node (ref "F13") (pin "2'") (pinfunction "2_2'") (pintype "passive"))
      (node (ref "X13") (pin "1") (pinfunction "1_1") (pintype "passive"))
      (node (ref "X13") (pin "1'") (pinfunction "1_1'") (pintype "passive"))
    )
    (net (code "29") (name "Net-(K1A-2)") (class "Default")
      (node (ref "K1") (pin "A2") (pinfunction "2_A2") (pintype "passive"))
      (node (ref "Q1") (pin "3") (pinfunction "C_3") (pintype "passive"))
      (node (ref "V5") (pin "A") (pinfunction "A_A") (pintype "passive"))
    )
    (net (code "30") (name "Net-(K1B-O)") (class "Default")
      (node (ref "K1") (pin "12") (pinfunction "O_12") (pintype "passive"))
      (node (ref "X1") (pin "1") (pinfunction "1_1") (pintype "passive"))
      (node (ref "X1") (pin "1'") (pinfunction "1_1'") (pintype "passive"))
    )
    (net (code "31") (name "Net-(K1B-P)") (class "Default")
      (node (ref "F1") (pin "2") (pinfunction "2_2") (pintype "passive"))
      (node (ref "F1") (pin "2'") (pinfunction "2_2'") (pintype "passive"))
      (node (ref "K1") (pin "11") (pinfunction "P_11") (pintype "passive"))
    )
    (net (code "32") (name "Net-(K1B-S)") (class "Default")
      (node (ref "K1") (pin "14") (pinfunction "S_14") (pintype "passive"))
      (node (ref "X1") (pin "3") (pinfunction "3_3") (pintype "passive"))
      (node (ref "X1") (pin "3'") (pinfunction "3_3'") (pintype "passive"))
    )
    (net (code "33") (name "Net-(K2A-2)") (class "Default")
      (node (ref "K2") (pin "A2") (pinfunction "2_A2") (pintype "passive"))
      (node (ref "Q2") (pin "3") (pinfunction "C_3") (pintype "passive"))
      (node (ref "V6") (pin "A") (pinfunction "A_A") (pintype "passive"))
    )
    (net (code "34") (name "Net-(K2B-O)") (class "Default")
      (node (ref "K2") (pin "12") (pinfunction "O_12") (pintype "passive"))
      (node (ref "X2") (pin "1") (pinfunction "1_1") (pintype "passive"))
      (node (ref "X2") (pin "1'") (pinfunction "1_1'") (pintype "passive"))
    )
    (net (code "35") (name "Net-(K2B-P)") (class "Default")
      (node (ref "F2") (pin "2") (pinfunction "2_2") (pintype "passive"))
      (node (ref "F2") (pin "2'") (pinfunction "2_2'") (pintype "passive"))
      (node (ref "K2") (pin "11") (pinfunction "P_11") (pintype "passive"))
    )
    (net (code "36") (name "Net-(K2B-S)") (class "Default")
      (node (ref "K2") (pin "14") (pinfunction "S_14") (pintype "passive"))
      (node (ref "X2") (pin "3") (pinfunction "3_3") (pintype "passive"))
      (node (ref "X2") (pin "3'") (pinfunction "3_3'") (pintype "passive"))
    )
    (net (code "37") (name "Net-(K3A-2)") (class "Default")
      (node (ref "K3") (pin "A2") (pinfunction "2_A2") (pintype "passive"))
      (node (ref "Q3") (pin "3") (pinfunction "C_3") (pintype "passive"))
      (node (ref "V7") (pin "A") (pinfunction "A_A") (pintype "passive"))
    )
    (net (code "38") (name "Net-(K3B-O)") (class "Default")
      (node (ref "K3") (pin "12") (pinfunction "O_12") (pintype "passive"))
      (node (ref "X3") (pin "1") (pinfunction "1_1") (pintype "passive"))
      (node (ref "X3") (pin "1'") (pinfunction "1_1'") (pintype "passive"))
    )
    (net (code "39") (name "Net-(K3B-P)") (class "Default")
      (node (ref "F3") (pin "2") (pinfunction "2_2") (pintype "passive"))
      (node (ref "F3") (pin "2'") (pinfunction "2_2'") (pintype "passive"))
      (node (ref "K3") (pin "11") (pinfunction "P_11") (pintype "passive"))
    )
    (net (code "40") (name "Net-(K3B-S)") (class "Default")
      (node (ref "K3") (pin "14") (pinfunction "S_14") (pintype "passive"))
      (node (ref "X3") (pin "3") (pinfunction "3_3") (pintype "passive"))
      (node (ref "X3") (pin "3'") (pinfunction "3_3'") (pintype "passive"))
    )
    (net (code "41") (name "Net-(K4A-2)") (class "Default")
      (node (ref "K4") (pin "A2") (pinfunction "2_A2") (pintype "passive"))
      (node (ref "Q4") (pin "3") (pinfunction "C_3") (pintype "passive"))
      (node (ref "V8") (pin "A") (pinfunction "A_A") (pintype "passive"))
    )
    (net (code "42") (name "Net-(K4B-O)") (class "Default")
      (node (ref "K4") (pin "12") (pinfunction "O_12") (pintype "passive"))
      (node (ref "X4") (pin "1") (pinfunction "1_1") (pintype "passive"))
      (node (ref "X4") (pin "1'") (pinfunction "1_1'") (pintype "passive"))
    )
    (net (code "43") (name "Net-(K4B-P)") (class "Default")
      (node (ref "F4") (pin "2") (pinfunction "2_2") (pintype "passive"))
      (node (ref "F4") (pin "2'") (pinfunction "2_2'") (pintype "passive"))
      (node (ref "K4") (pin "11") (pinfunction "P_11") (pintype "passive"))
    )
    (net (code "44") (name "Net-(K4B-S)") (class "Default")
      (node (ref "K4") (pin "14") (pinfunction "S_14") (pintype "passive"))
      (node (ref "X4") (pin "3") (pinfunction "3_3") (pintype "passive"))
      (node (ref "X4") (pin "3'") (pinfunction "3_3'") (pintype "passive"))
    )
    (net (code "45") (name "Net-(K5A-2)") (class "Default")
      (node (ref "K5") (pin "A2") (pinfunction "2_A2") (pintype "passive"))
      (node (ref "Q5") (pin "3") (pinfunction "C_3") (pintype "passive"))
      (node (ref "V13") (pin "A") (pinfunction "A_A") (pintype "passive"))
    )
    (net (code "46") (name "Net-(K5B-O)") (class "Default")
      (node (ref "K5") (pin "12") (pinfunction "O_12") (pintype "passive"))
      (node (ref "X5") (pin "1") (pinfunction "1_1") (pintype "passive"))
      (node (ref "X5") (pin "1'") (pinfunction "1_1'") (pintype "passive"))
    )
    (net (code "47") (name "Net-(K5B-P)") (class "Default")
      (node (ref "F5") (pin "2") (pinfunction "2_2") (pintype "passive"))
      (node (ref "F5") (pin "2'") (pinfunction "2_2'") (pintype "passive"))
      (node (ref "K5") (pin "11") (pinfunction "P_11") (pintype "passive"))
    )
    (net (code "48") (name "Net-(K5B-S)") (class "Default")
      (node (ref "K5") (pin "14") (pinfunction "S_14") (pintype "passive"))
      (node (ref "X5") (pin "3") (pinfunction "3_3") (pintype "passive"))
      (node (ref "X5") (pin "3'") (pinfunction "3_3'") (pintype "passive"))
    )
    (net (code "49") (name "Net-(K6A-2)") (class "Default")
      (node (ref "K6") (pin "A2") (pinfunction "2_A2") (pintype "passive"))
      (node (ref "Q6") (pin "3") (pinfunction "C_3") (pintype "passive"))
      (node (ref "V14") (pin "A") (pinfunction "A_A") (pintype "passive"))
    )
    (net (code "50") (name "Net-(K6B-O)") (class "Default")
      (node (ref "K6") (pin "12") (pinfunction "O_12") (pintype "passive"))
      (node (ref "X6") (pin "1") (pinfunction "1_1") (pintype "passive"))
      (node (ref "X6") (pin "1'") (pinfunction "1_1'") (pintype "passive"))
    )
    (net (code "51") (name "Net-(K6B-P)") (class "Default")
      (node (ref "F6") (pin "2") (pinfunction "2_2") (pintype "passive"))
      (node (ref "F6") (pin "2'") (pinfunction "2_2'") (pintype "passive"))
      (node (ref "K6") (pin "11") (pinfunction "P_11") (pintype "passive"))
    )
    (net (code "52") (name "Net-(K6B-S)") (class "Default")
      (node (ref "K6") (pin "14") (pinfunction "S_14") (pintype "passive"))
      (node (ref "X6") (pin "3") (pinfunction "3_3") (pintype "passive"))
      (node (ref "X6") (pin "3'") (pinfunction "3_3'") (pintype "passive"))
    )
    (net (code "53") (name "Net-(K7A-2)") (class "Default")
      (node (ref "K7") (pin "A2") (pinfunction "2_A2") (pintype "passive"))
      (node (ref "Q7") (pin "3") (pinfunction "C_3") (pintype "passive"))
      (node (ref "V15") (pin "A") (pinfunction "A_A") (pintype "passive"))
    )
    (net (code "54") (name "Net-(K7B-O)") (class "Default")
      (node (ref "K7") (pin "12") (pinfunction "O_12") (pintype "passive"))
      (node (ref "X7") (pin "1") (pinfunction "1_1") (pintype "passive"))
      (node (ref "X7") (pin "1'") (pinfunction "1_1'") (pintype "passive"))
    )
    (net (code "55") (name "Net-(K7B-P)") (class "Default")
      (node (ref "F7") (pin "2") (pinfunction "2_2") (pintype "passive"))
      (node (ref "F7") (pin "2'") (pinfunction "2_2'") (pintype "passive"))
      (node (ref "K7") (pin "11") (pinfunction "P_11") (pintype "passive"))
    )
    (net (code "56") (name "Net-(K7B-S)") (class "Default")
      (node (ref "K7") (pin "14") (pinfunction "S_14") (pintype "passive"))
      (node (ref "X7") (pin "3") (pinfunction "3_3") (pintype "passive"))
      (node (ref "X7") (pin "3'") (pinfunction "3_3'") (pintype "passive"))
    )
    (net (code "57") (name "Net-(K8A-2)") (class "Default")
      (node (ref "K8") (pin "A2") (pinfunction "2_A2") (pintype "passive"))
      (node (ref "Q8") (pin "3") (pinfunction "C_3") (pintype "passive"))
      (node (ref "V16") (pin "A") (pinfunction "A_A") (pintype "passive"))
    )
    (net (code "58") (name "Net-(K8B-O)") (class "Default")
      (node (ref "K8") (pin "12") (pinfunction "O_12") (pintype "passive"))
      (node (ref "X8") (pin "1") (pinfunction "1_1") (pintype "passive"))
      (node (ref "X8") (pin "1'") (pinfunction "1_1'") (pintype "passive"))
    )
    (net (code "59") (name "Net-(K8B-P)") (class "Default")
      (node (ref "F8") (pin "2") (pinfunction "2_2") (pintype "passive"))
      (node (ref "F8") (pin "2'") (pinfunction "2_2'") (pintype "passive"))
      (node (ref "K8") (pin "11") (pinfunction "P_11") (pintype "passive"))
    )
    (net (code "60") (name "Net-(K8B-S)") (class "Default")
      (node (ref "K8") (pin "14") (pinfunction "S_14") (pintype "passive"))
      (node (ref "X8") (pin "3") (pinfunction "3_3") (pintype "passive"))
      (node (ref "X8") (pin "3'") (pinfunction "3_3'") (pintype "passive"))
    )
    (net (code "61") (name "Net-(K9A-2)") (class "Default")
      (node (ref "K9") (pin "A2") (pinfunction "2_A2") (pintype "passive"))
      (node (ref "Q9") (pin "3") (pinfunction "C_3") (pintype "passive"))
      (node (ref "V18") (pin "A") (pinfunction "A_A") (pintype "passive"))
    )
    (net (code "62") (name "Net-(K9B-O)") (class "Default")
      (node (ref "K9") (pin "12") (pinfunction "O_12") (pintype "passive"))
      (node (ref "X9") (pin "1") (pinfunction "1_1") (pintype "passive"))
      (node (ref "X9") (pin "1'") (pinfunction "1_1'") (pintype "passive"))
    )
    (net (code "63") (name "Net-(K9B-P)") (class "Default")
      (node (ref "F9") (pin "2") (pinfunction "2_2") (pintype "passive"))
      (node (ref "F9") (pin "2'") (pinfunction "2_2'") (pintype "passive"))
      (node (ref "K9") (pin "11") (pinfunction "P_11") (pintype "passive"))
    )
    (net (code "64") (name "Net-(K9B-S)") (class "Default")
      (node (ref "K9") (pin "14") (pinfunction "S_14") (pintype "passive"))
      (node (ref "X9") (pin "3") (pinfunction "3_3") (pintype "passive"))
      (node (ref "X9") (pin "3'") (pinfunction "3_3'") (pintype "passive"))
    )
    (net (code "65") (name "Net-(Q1-B)") (class "Default")
      (node (ref "Q1") (pin "1") (pinfunction "B_1") (pintype "passive"))
      (node (ref "R9") (pin "2") (pinfunction "2_2") (pintype "passive"))
    )
    (net (code "66") (name "Net-(Q2-B)") (class "Default")
      (node (ref "Q2") (pin "1") (pinfunction "B_1") (pintype "passive"))
      (node (ref "R10") (pin "2") (pinfunction "2_2") (pintype "passive"))
    )
    (net (code "67") (name "Net-(Q3-B)") (class "Default")
      (node (ref "Q3") (pin "1") (pinfunction "B_1") (pintype "passive"))
      (node (ref "R11") (pin "2") (pinfunction "2_2") (pintype "passive"))
    )
    (net (code "68") (name "Net-(Q4-B)") (class "Default")
      (node (ref "Q4") (pin "1") (pinfunction "B_1") (pintype "passive"))
      (node (ref "R12") (pin "2") (pinfunction "2_2") (pintype "passive"))
    )
    (net (code "69") (name "Net-(Q5-B)") (class "Default")
      (node (ref "Q5") (pin "1") (pinfunction "B_1") (pintype "passive"))
      (node (ref "R21") (pin "2") (pinfunction "2_2") (pintype "passive"))
    )
    (net (code "70") (name "Net-(Q6-B)") (class "Default")
      (node (ref "Q6") (pin "1") (pinfunction "B_1") (pintype "passive"))
      (node (ref "R22") (pin "2") (pinfunction "2_2") (pintype "passive"))
    )
    (net (code "71") (name "Net-(Q7-B)") (class "Default")
      (node (ref "Q7") (pin "1") (pinfunction "B_1") (pintype "passive"))
      (node (ref "R23") (pin "2") (pinfunction "2_2") (pintype "passive"))
    )
    (net (code "72") (name "Net-(Q8-B)") (class "Default")
      (node (ref "Q8") (pin "1") (pinfunction "B_1") (pintype "passive"))
      (node (ref "R24") (pin "2") (pinfunction "2_2") (pintype "passive"))
    )
    (net (code "73") (name "Net-(Q9-B)") (class "Default")
      (node (ref "Q9") (pin "1") (pinfunction "B_1") (pintype "passive"))
      (node (ref "R27") (pin "2") (pinfunction "2_2") (pintype "passive"))
    )
    (net (code "74") (name "Net-(S1-P)") (class "Default")
      (node (ref "R5") (pin "2") (pinfunction "2_2") (pintype "passive"))
      (node (ref "R9") (pin "1") (pinfunction "1_1") (pintype "passive"))
      (node (ref "S1") (pin "2") (pinfunction "P_2") (pintype "passive"))
      (node (ref "V1") (pin "3") (pinfunction "C_3") (pintype "passive"))
    )
    (net (code "75") (name "Net-(S2-P)") (class "Default")
      (node (ref "R10") (pin "1") (pinfunction "1_1") (pintype "passive"))
      (node (ref "R6") (pin "2") (pinfunction "2_2") (pintype "passive"))
      (node (ref "S2") (pin "2") (pinfunction "P_2") (pintype "passive"))
      (node (ref "V2") (pin "3") (pinfunction "C_3") (pintype "passive"))
    )
    (net (code "76") (name "Net-(S3-P)") (class "Default")
      (node (ref "R11") (pin "1") (pinfunction "1_1") (pintype "passive"))
      (node (ref "R7") (pin "2") (pinfunction "2_2") (pintype "passive"))
      (node (ref "S3") (pin "2") (pinfunction "P_2") (pintype "passive"))
      (node (ref "V3") (pin "3") (pinfunction "C_3") (pintype "passive"))
    )
    (net (code "77") (name "Net-(S4-P)") (class "Default")
      (node (ref "R12") (pin "1") (pinfunction "1_1") (pintype "passive"))
      (node (ref "R8") (pin "2") (pinfunction "2_2") (pintype "passive"))
      (node (ref "S4") (pin "2") (pinfunction "P_2") (pintype "passive"))
      (node (ref "V4") (pin "3") (pinfunction "C_3") (pintype "passive"))
    )
    (net (code "78") (name "Net-(S5-P)") (class "Default")
      (node (ref "R17") (pin "2") (pinfunction "2_2") (pintype "passive"))
      (node (ref "R21") (pin "1") (pinfunction "1_1") (pintype "passive"))
      (node (ref "S5") (pin "2") (pinfunction "P_2") (pintype "passive"))
      (node (ref "V9") (pin "3") (pinfunction "C_3") (pintype "passive"))
    )
    (net (code "79") (name "Net-(S6-P)") (class "Default")
      (node (ref "R18") (pin "2") (pinfunction "2_2") (pintype "passive"))
      (node (ref "R22") (pin "1") (pinfunction "1_1") (pintype "passive"))
      (node (ref "S6") (pin "2") (pinfunction "P_2") (pintype "passive"))
      (node (ref "V10") (pin "3") (pinfunction "C_3") (pintype "passive"))
    )
    (net (code "80") (name "Net-(S7-P)") (class "Default")
      (node (ref "R19") (pin "2") (pinfunction "2_2") (pintype "passive"))
      (node (ref "R23") (pin "1") (pinfunction "1_1") (pintype "passive"))
      (node (ref "S7") (pin "2") (pinfunction "P_2") (pintype "passive"))
      (node (ref "V11") (pin "3") (pinfunction "C_3") (pintype "passive"))
    )
    (net (code "81") (name "Net-(S8-P)") (class "Default")
      (node (ref "R20") (pin "2") (pinfunction "2_2") (pintype "passive"))
      (node (ref "R24") (pin "1") (pinfunction "1_1") (pintype "passive"))
      (node (ref "S8") (pin "2") (pinfunction "P_2") (pintype "passive"))
      (node (ref "V12") (pin "3") (pinfunction "C_3") (pintype "passive"))
    )
    (net (code "82") (name "Net-(S9-P)") (class "Default")
      (node (ref "R26") (pin "2") (pinfunction "2_2") (pintype "passive"))
      (node (ref "R27") (pin "1") (pinfunction "1_1") (pintype "passive"))
      (node (ref "S9") (pin "2") (pinfunction "P_2") (pintype "passive"))
      (node (ref "V17") (pin "3") (pinfunction "C_3") (pintype "passive"))
    )
    (net (code "83") (name "Net-(V1-A)") (class "Default")
      (node (ref "R1") (pin "1") (pinfunction "1_1") (pintype "passive"))
      (node (ref "V1") (pin "1") (pinfunction "A_1") (pintype "passive"))
    )
    (net (code "84") (name "Net-(V2-A)") (class "Default")
      (node (ref "R2") (pin "1") (pinfunction "1_1") (pintype "passive"))
      (node (ref "V2") (pin "1") (pinfunction "A_1") (pintype "passive"))
    )
    (net (code "85") (name "Net-(V3-A)") (class "Default")
      (node (ref "R3") (pin "1") (pinfunction "1_1") (pintype "passive"))
      (node (ref "V3") (pin "1") (pinfunction "A_1") (pintype "passive"))
    )
    (net (code "86") (name "Net-(V4-A)") (class "Default")
      (node (ref "R4") (pin "1") (pinfunction "1_1") (pintype "passive"))
      (node (ref "V4") (pin "1") (pinfunction "A_1") (pintype "passive"))
    )
    (net (code "87") (name "Net-(V9-A)") (class "Default")
      (node (ref "R13") (pin "1") (pinfunction "1_1") (pintype "passive"))
      (node (ref "V9") (pin "1") (pinfunction "A_1") (pintype "passive"))
    )
    (net (code "88") (name "Net-(V10-A)") (class "Default")
      (node (ref "R14") (pin "1") (pinfunction "1_1") (pintype "passive"))
      (node (ref "V10") (pin "1") (pinfunction "A_1") (pintype "passive"))
    )
    (net (code "89") (name "Net-(V11-A)") (class "Default")
      (node (ref "R15") (pin "1") (pinfunction "1_1") (pintype "passive"))
      (node (ref "V11") (pin "1") (pinfunction "A_1") (pintype "passive"))
    )
    (net (code "90") (name "Net-(V12-A)") (class "Default")
      (node (ref "R16") (pin "1") (pinfunction "1_1") (pintype "passive"))
      (node (ref "V12") (pin "1") (pinfunction "A_1") (pintype "passive"))
    )
    (net (code "91") (name "Net-(V17-A)") (class "Default")
      (node (ref "R25") (pin "1") (pinfunction "1_1") (pintype "passive"))
      (node (ref "V17") (pin "1") (pinfunction "A_1") (pintype "passive"))
    )
    (net (code "92") (name "P1") (class "Default")
      (node (ref "JP1") (pin "6") (pinfunction "6_6") (pintype "passive"))
      (node (ref "R1") (pin "2") (pinfunction "2_2") (pintype "passive"))
    )
    (net (code "93") (name "P2") (class "Default")
      (node (ref "JP1") (pin "4") (pinfunction "4_4") (pintype "passive"))
      (node (ref "R2") (pin "2") (pinfunction "2_2") (pintype "passive"))
    )
    (net (code "94") (name "P3") (class "Default")
      (node (ref "JP1") (pin "2") (pinfunction "2_2") (pintype "passive"))
      (node (ref "R3") (pin "2") (pinfunction "2_2") (pintype "passive"))
    )
    (net (code "95") (name "P4") (class "Default")
      (node (ref "JP1") (pin "1") (pinfunction "1_1") (pintype "passive"))
      (node (ref "R4") (pin "2") (pinfunction "2_2") (pintype "passive"))
    )
    (net (code "96") (name "P5") (class "Default")
      (node (ref "JP1") (pin "3") (pinfunction "3_3") (pintype "passive"))
      (node (ref "R13") (pin "2") (pinfunction "2_2") (pintype "passive"))
    )
    (net (code "97") (name "P6") (class "Default")
      (node (ref "JP1") (pin "5") (pinfunction "5_5") (pintype "passive"))
      (node (ref "R14") (pin "2") (pinfunction "2_2") (pintype "passive"))
    )
    (net (code "98") (name "P7") (class "Default")
      (node (ref "JP1") (pin "11") (pinfunction "11_11") (pintype "passive"))
      (node (ref "R15") (pin "2") (pinfunction "2_2") (pintype "passive"))
    )
    (net (code "99") (name "P8") (class "Default")
      (node (ref "JP1") (pin "13") (pinfunction "13_13") (pintype "passive"))
      (node (ref "R16") (pin "2") (pinfunction "2_2") (pintype "passive"))
    )
    (net (code "100") (name "P9") (class "Default")
      (node (ref "JP1") (pin "15") (pinfunction "15_15") (pintype "passive"))
      (node (ref "R25") (pin "2") (pinfunction "2_2") (pintype "passive"))
    )
    (net (code "101") (name "PE") (class "Default")
      (node (ref "X1") (pin "5") (pinfunction "5_5") (pintype "passive"))
      (node (ref "X1") (pin "5'") (pinfunction "5_5'") (pintype "passive"))
      (node (ref "X10") (pin "3") (pinfunction "3_3") (pintype "passive"))
      (node (ref "X10") (pin "3'") (pinfunction "3_3'") (pintype "passive"))
      (node (ref "X14") (pin "L3.1") (pinfunction "P3.1_L3.1") (pintype "bidirectional"))
      (node (ref "X14") (pin "L3.2") (pinfunction "P3.2_L3.2") (pintype "bidirectional"))
      (node (ref "X2") (pin "5") (pinfunction "5_5") (pintype "passive"))
      (node (ref "X2") (pin "5'") (pinfunction "5_5'") (pintype "passive"))
      (node (ref "X3") (pin "5") (pinfunction "5_5") (pintype "passive"))
      (node (ref "X3") (pin "5'") (pinfunction "5_5'") (pintype "passive"))
      (node (ref "X4") (pin "5") (pinfunction "5_5") (pintype "passive"))
      (node (ref "X4") (pin "5'") (pinfunction "5_5'") (pintype "passive"))
      (node (ref "X5") (pin "5") (pinfunction "5_5") (pintype "passive"))
      (node (ref "X5") (pin "5'") (pinfunction "5_5'") (pintype "passive"))
      (node (ref "X6") (pin "5") (pinfunction "5_5") (pintype "passive"))
      (node (ref "X6") (pin "5'") (pinfunction "5_5'") (pintype "passive"))
      (node (ref "X7") (pin "5") (pinfunction "5_5") (pintype "passive"))
      (node (ref "X7") (pin "5'") (pinfunction "5_5'") (pintype "passive"))
      (node (ref "X8") (pin "5") (pinfunction "5_5") (pintype "passive"))
      (node (ref "X8") (pin "5'") (pinfunction "5_5'") (pintype "passive"))
      (node (ref "X9") (pin "5") (pinfunction "5_5") (pintype "passive"))
      (node (ref "X9") (pin "5'") (pinfunction "5_5'") (pintype "passive"))
    )
    (net (code "102") (name "SCHIRM") (class "Default")
      (node (ref "X13") (pin "5") (pinfunction "5_5") (pintype "passive"))
      (node (ref "X13") (pin "5'") (pinfunction "5_5'") (pintype "passive"))
    )
    (net (code "103") (name "unconnected-(JP1-Pad14)") (class "Default")
      (node (ref "JP1") (pin "14") (pinfunction "14_14") (pintype "passive"))
    )
    (net (code "104") (name "unconnected-(JP1-Pad16)") (class "Default")
      (node (ref "JP1") (pin "16") (pinfunction "16_16") (pintype "passive"))
    )
    (net (code "105") (name "unconnected-(JP1-Pad17)") (class "Default")
      (node (ref "JP1") (pin "17") (pinfunction "17_17") (pintype "passive"))
    )
    (net (code "106") (name "unconnected-(JP1-Pad18)") (class "Default")
      (node (ref "JP1") (pin "18") (pinfunction "18_18") (pintype "passive"))
    )
  )
)
